# control-board.net
KiCad netlist of a schematic drawn in EAGLE
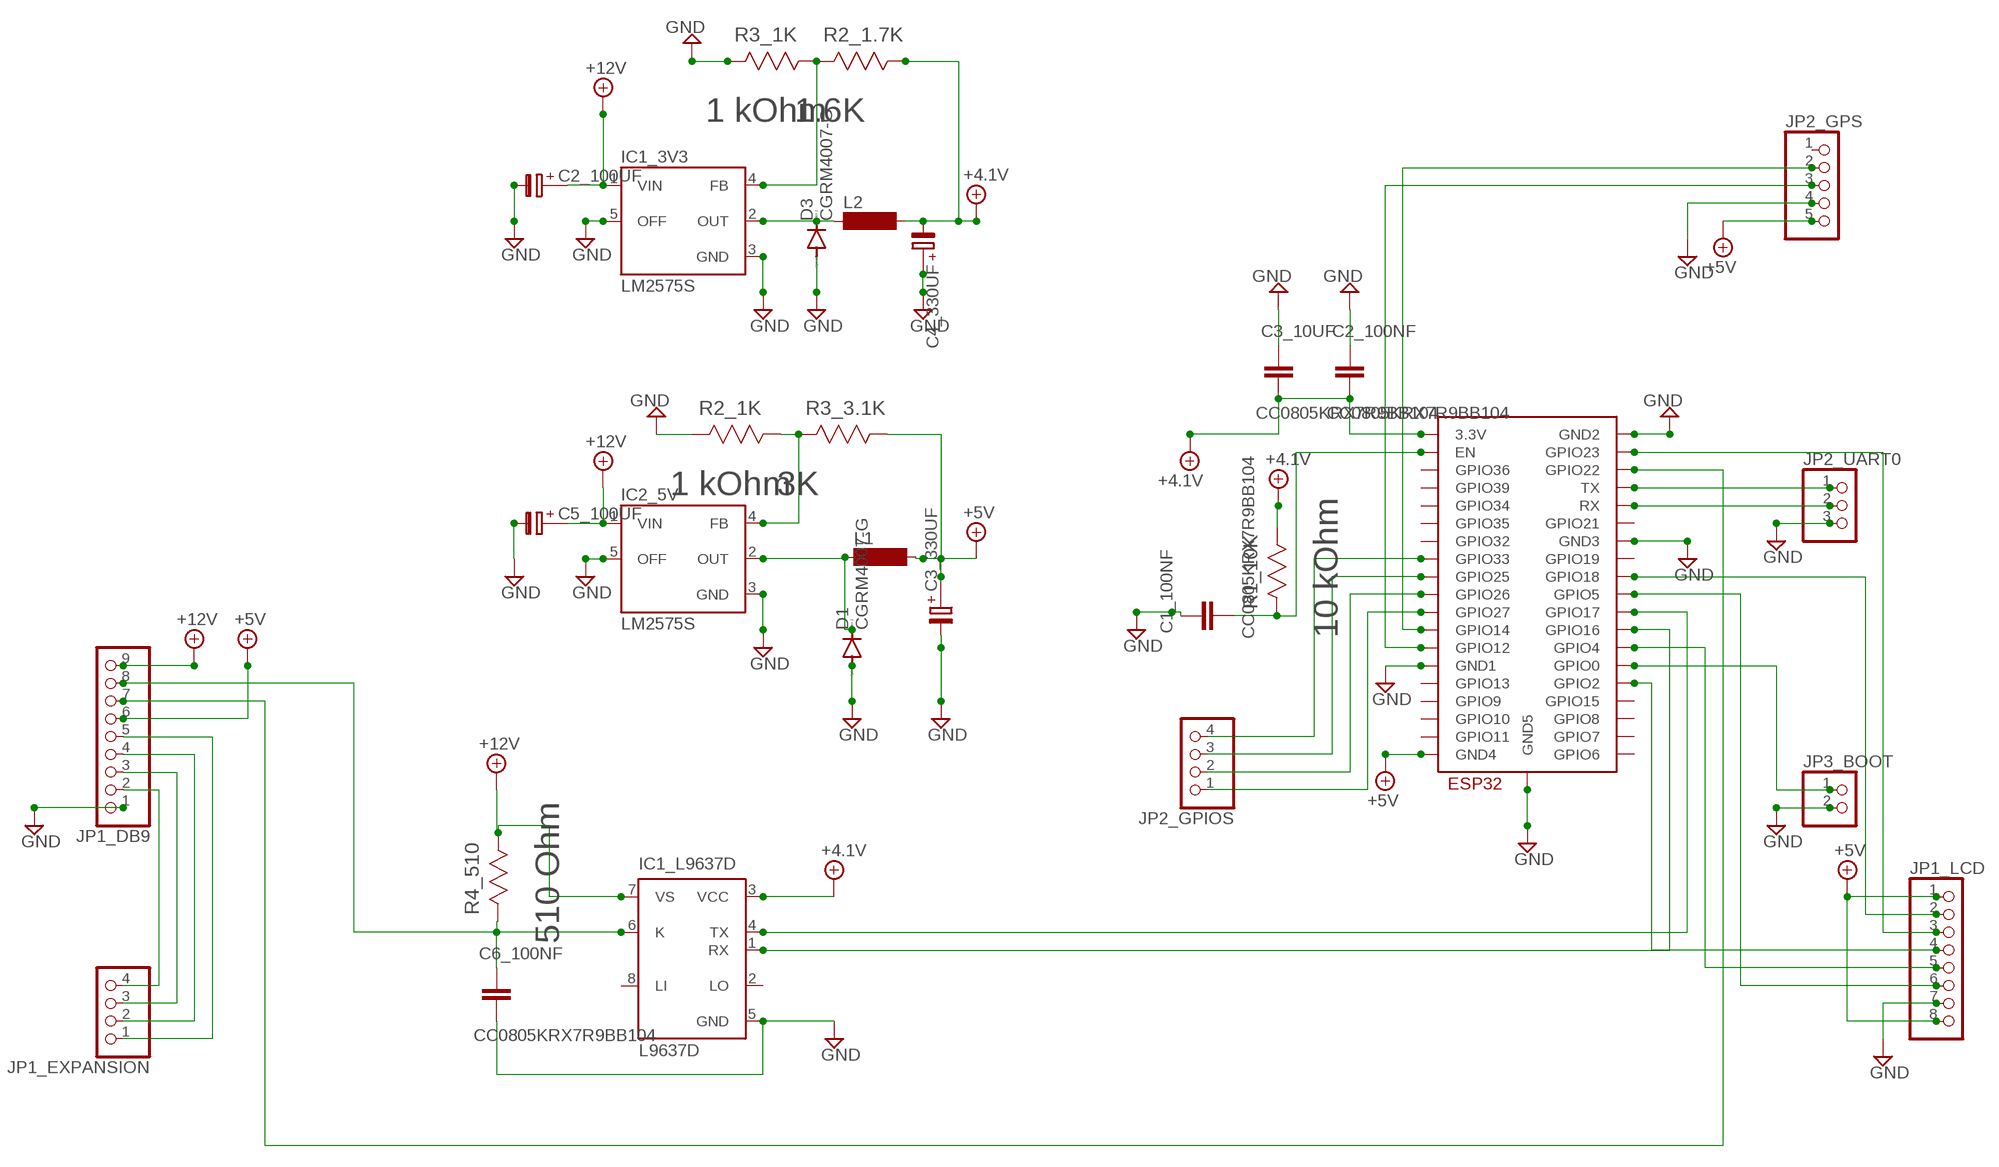
[diagram p0: schematic, sheet 1]

(export (version "E")
  (design (tool "Eeschema 10.0.6"))
  (components
    (comp (ref "C1_100NF")
      (value "CC0805KRX7R9BB104")
      (footprint "eagle-import:CAP_0805")
      (fields
        (field (name "DIGIKEY_PART_NUMBER") "311-1140-2-ND")
        (field (name "MANUFACTURER") "Yageo")
        (field (name "CREATED_BY") "PCBLayout.com")
      )
      (libsource (lib "eagle-import") (part "CC0805KRX7R9BB104"))
    )
    (comp (ref "C2_100NF")
      (value "CC0805KRX7R9BB104")
      (footprint "eagle-import:CAP_0805")
      (fields
        (field (name "DIGIKEY_PART_NUMBER") "311-1140-2-ND")
        (field (name "MANUFACTURER") "Yageo")
        (field (name "CREATED_BY") "PCBLayout.com")
      )
      (libsource (lib "eagle-import") (part "CC0805KRX7R9BB104"))
    )
    (comp (ref "C2_100UF")
      (value "C-PR-SMD-SV-E/F")
      (footprint "eagle-import:SV-E_F")
      (libsource (lib "eagle-import") (part "C-PR-SMD-SV-E/F"))
    )
    (comp (ref "C3_10UF")
      (value "CC0805KRX7R9BB104")
      (footprint "eagle-import:CAP_0805")
      (fields
        (field (name "DIGIKEY_PART_NUMBER") "311-1140-2-ND")
        (field (name "MANUFACTURER") "Yageo")
        (field (name "CREATED_BY") "PCBLayout.com")
      )
      (libsource (lib "eagle-import") (part "CC0805KRX7R9BB104"))
    )
    (comp (ref "C3_330UF")
      (value "C-PR-SMD-SV-D")
      (footprint "eagle-import:SV-D")
      (libsource (lib "eagle-import") (part "C-PR-SMD-SV-D"))
    )
    (comp (ref "C4_330UF")
      (value "C-PR-SMD-SV-D")
      (footprint "eagle-import:SV-D")
      (libsource (lib "eagle-import") (part "C-PR-SMD-SV-D"))
    )
    (comp (ref "C5_100UF")
      (value "C-PR-SMD-SV-E/F")
      (footprint "eagle-import:SV-E_F")
      (libsource (lib "eagle-import") (part "C-PR-SMD-SV-E/F"))
    )
    (comp (ref "C6_100NF")
      (value "CC0805KRX7R9BB104")
      (footprint "eagle-import:CAP_0805")
      (fields
        (field (name "DIGIKEY_PART_NUMBER") "311-1140-2-ND")
        (field (name "MANUFACTURER") "Yageo")
        (field (name "CREATED_BY") "PCBLayout.com")
      )
      (libsource (lib "eagle-import") (part "CC0805KRX7R9BB104"))
    )
    (comp (ref "D1")
      (value "CGRM4007-G")
      (footprint "eagle-import:SOD-123_MINI-SMA")
      (libsource (lib "eagle-import") (part "CGRM400-G7"))
    )
    (comp (ref "D3")
      (value "CGRM4007-G")
      (footprint "eagle-import:SOD-123_MINI-SMA")
      (libsource (lib "eagle-import") (part "CGRM400-G7"))
    )
    (comp (ref "ESP32")
      (value "ESP32-WROOM")
      (footprint "eagle-import:ESP32-WROOM")
      (libsource (lib "eagle-import") (part "ESP32-WROOM"))
    )
    (comp (ref "IC1_3V3")
      (value "LM2575S")
      (footprint "eagle-import:TO263-5")
      (libsource (lib "eagle-import") (part "LM2575S"))
    )
    (comp (ref "IC1_L9637D")
      (value "L9637D")
      (footprint "eagle-import:SO08")
      (libsource (lib "eagle-import") (part "L9637D"))
    )
    (comp (ref "IC2_5V")
      (value "LM2575S")
      (footprint "eagle-import:TO263-5")
      (libsource (lib "eagle-import") (part "LM2575S"))
    )
    (comp (ref "JP1_DB9")
      (value "PINHD-1X9/90")
      (footprint "eagle-import:1X09_90")
      (libsource (lib "eagle-import") (part "PINHD-1X9/90"))
    )
    (comp (ref "JP1_EXPANSION")
      (value "PINHD-1X4/90")
      (footprint "eagle-import:1X04_90")
      (libsource (lib "eagle-import") (part "PINHD-1X4/90"))
    )
    (comp (ref "JP1_LCD")
      (value "PINHD-1X8")
      (footprint "eagle-import:1X08")
      (libsource (lib "eagle-import") (part "PINHD-1X8"))
    )
    (comp (ref "JP2_GPIOS")
      (value "PINHD-1X4/90")
      (footprint "eagle-import:1X04_90")
      (libsource (lib "eagle-import") (part "PINHD-1X4/90"))
    )
    (comp (ref "JP2_GPS")
      (value "PINHD-1X5")
      (footprint "eagle-import:1X05")
      (libsource (lib "eagle-import") (part "PINHD-1X5"))
    )
    (comp (ref "JP2_UART0")
      (value "PINHD-1X3/90")
      (footprint "eagle-import:1X03_90")
      (libsource (lib "eagle-import") (part "PINHD-1X3/90"))
    )
    (comp (ref "JP3_BOOT")
      (value "PINHD-1X2/90")
      (footprint "eagle-import:1X02_90")
      (libsource (lib "eagle-import") (part "PINHD-1X2/90"))
    )
    (comp (ref "L1")
      (value "MS85")
      (footprint "eagle-import:MS85")
      (libsource (lib "eagle-import") (part "MS85"))
    )
    (comp (ref "L2")
      (value "MS85")
      (footprint "eagle-import:MS85")
      (libsource (lib "eagle-import") (part "MS85"))
    )
    (comp (ref "R1_10K")
      (value "10 kOhm")
      (footprint "eagle-import:RESC2013X65N")
      (fields (field (name "MPN") "ERA-6AEB103V") (field (name "TOLERANCE") "±0.1 %"))
      (libsource (lib "eagle-import") (part "ERA-6AEB103V"))
    )
    (comp (ref "R2_1.7K")
      (value "1.6K")
      (footprint "eagle-import:RESC2013X65N")
      (fields (field (name "MPN") "ERJP06F1601V") (field (name "TOLERANCE") "± 1%"))
      (libsource (lib "eagle-import") (part "ERJP06F1601V"))
    )
    (comp (ref "R2_1K")
      (value "1 kOhm")
      (footprint "eagle-import:RESC2013X65N")
      (fields (field (name "MPN") "ERA-6AEB102V") (field (name "TOLERANCE") "±0.1 %"))
      (libsource (lib "eagle-import") (part "ERA-6AEB102V"))
    )
    (comp (ref "R3_1K")
      (value "1 kOhm")
      (footprint "eagle-import:RESC2013X65N")
      (fields (field (name "MPN") "ERA-6AEB102V") (field (name "TOLERANCE") "±0.1 %"))
      (libsource (lib "eagle-import") (part "ERA-6AEB102V"))
    )
    (comp (ref "R3_3.1K")
      (value "3K")
      (footprint "eagle-import:RESC2013X65N")
      (fields (field (name "MPN") "ERJP06F3001V") (field (name "TOLERANCE") "± 1%"))
      (libsource (lib "eagle-import") (part "ERJP06F3001V"))
    )
    (comp (ref "R4_510")
      (value "510 Ohm")
      (footprint "eagle-import:RESC2013X65N")
      (fields (field (name "MPN") "ERA-6AEB511V") (field (name "TOLERANCE") "±0.1 %"))
      (libsource (lib "eagle-import") (part "ERA-6AEB511V"))
    )
  )
  (nets
    (net (code "1") (name "+4.1V") (class "Default")
      (node (ref "C2_100NF") (pin "2") (pinfunction "2_2") (pintype "passive"))
      (node (ref "C3_10UF") (pin "2") (pinfunction "2_2") (pintype "passive"))
      (node (ref "C4_330UF") (pin "-") (pinfunction "-_-") (pintype "passive"))
      (node (ref "ESP32") (pin "3V3") (pinfunction "3.3V_3V3") (pintype "bidirectional"))
      (node (ref "IC1_L9637D") (pin "3") (pinfunction "VCC_3") (pintype "power_in"))
      (node (ref "L2") (pin "2") (pinfunction "2_2") (pintype "passive"))
      (node (ref "R1_10K") (pin "1") (pinfunction "R1_1") (pintype "passive"))
      (node (ref "R2_1.7K") (pin "1") (pinfunction "R1_1") (pintype "passive"))
    )
    (net (code "2") (name "+5V") (class "Default")
      (node (ref "C3_330UF") (pin "+") (pinfunction "+_+") (pintype "passive"))
      (node (ref "ESP32") (pin "GND4") (pinfunction "GND4_GND4") (pintype "bidirectional"))
      (node (ref "JP1_DB9") (pin "6") (pinfunction "6_6") (pintype "passive"))
      (node (ref "JP1_LCD") (pin "1") (pinfunction "1_1") (pintype "passive"))
      (node (ref "JP1_LCD") (pin "8") (pinfunction "8_8") (pintype "passive"))
      (node (ref "JP2_GPS") (pin "5") (pinfunction "5_5") (pintype "passive"))
      (node (ref "L1") (pin "2") (pinfunction "2_2") (pintype "passive"))
      (node (ref "R3_3.1K") (pin "1") (pinfunction "R1_1") (pintype "passive"))
    )
    (net (code "3") (name "+12V") (class "Default")
      (node (ref "C2_100UF") (pin "+") (pinfunction "+_+") (pintype "passive"))
      (node (ref "C5_100UF") (pin "+") (pinfunction "+_+") (pintype "passive"))
      (node (ref "IC1_3V3") (pin "1") (pinfunction "VIN_1") (pintype "power_in"))
      (node (ref "IC1_L9637D") (pin "7") (pinfunction "VS_7") (pintype "power_in"))
      (node (ref "IC2_5V") (pin "1") (pinfunction "VIN_1") (pintype "power_in"))
      (node (ref "JP1_DB9") (pin "9") (pinfunction "9_9") (pintype "passive"))
      (node (ref "R4_510") (pin "1") (pinfunction "R1_1") (pintype "passive"))
    )
    (net (code "4") (name "GND") (class "Default")
      (node (ref "C1_100NF") (pin "1") (pinfunction "1_1") (pintype "passive"))
      (node (ref "C2_100NF") (pin "1") (pinfunction "1_1") (pintype "passive"))
      (node (ref "C2_100UF") (pin "-") (pinfunction "-_-") (pintype "passive"))
      (node (ref "C3_10UF") (pin "1") (pinfunction "1_1") (pintype "passive"))
      (node (ref "C3_330UF") (pin "-") (pinfunction "-_-") (pintype "passive"))
      (node (ref "C4_330UF") (pin "+") (pinfunction "+_+") (pintype "passive"))
      (node (ref "C5_100UF") (pin "-") (pinfunction "-_-") (pintype "passive"))
      (node (ref "C6_100NF") (pin "2") (pinfunction "2_2") (pintype "passive"))
      (node (ref "D1") (pin "A") (pinfunction "A_A") (pintype "passive"))
      (node (ref "D3") (pin "A") (pinfunction "A_A") (pintype "passive"))
      (node (ref "ESP32") (pin "GND1") (pinfunction "GND1_GND1") (pintype "bidirectional"))
      (node (ref "ESP32") (pin "GND2") (pinfunction "GND2_GND2") (pintype "bidirectional"))
      (node (ref "ESP32") (pin "GND3") (pinfunction "GND3_GND3") (pintype "bidirectional"))
      (node (ref "ESP32") (pin "GND5") (pinfunction "GND5_GND5") (pintype "bidirectional"))
      (node (ref "IC1_3V3") (pin "3") (pinfunction "GND_3") (pintype "power_in"))
      (node (ref "IC1_3V3") (pin "5") (pinfunction "OFF_5") (pintype "input"))
      (node (ref "IC1_L9637D") (pin "5") (pinfunction "GND_5") (pintype "power_in"))
      (node (ref "IC2_5V") (pin "3") (pinfunction "GND_3") (pintype "power_in"))
      (node (ref "IC2_5V") (pin "5") (pinfunction "OFF_5") (pintype "input"))
      (node (ref "JP1_DB9") (pin "1") (pinfunction "1_1") (pintype "passive"))
      (node (ref "JP1_LCD") (pin "7") (pinfunction "7_7") (pintype "passive"))
      (node (ref "JP2_GPS") (pin "4") (pinfunction "4_4") (pintype "passive"))
      (node (ref "JP2_UART0") (pin "3") (pinfunction "3_3") (pintype "passive"))
      (node (ref "JP3_BOOT") (pin "2") (pinfunction "2_2") (pintype "passive"))
      (node (ref "R2_1K") (pin "2") (pinfunction "R2_2") (pintype "passive"))
      (node (ref "R3_1K") (pin "2") (pinfunction "R2_2") (pintype "passive"))
    )
    (net (code "5") (name "Net-(ESP32-GPIO0)") (class "Default")
      (node (ref "ESP32") (pin "IO0") (pinfunction "GPIO0_IO0") (pintype "bidirectional"))
      (node (ref "JP3_BOOT") (pin "1") (pinfunction "1_1") (pintype "passive"))
    )
    (net (code "6") (name "Net-(ESP32-GPIO2)") (class "Default")
      (node (ref "ESP32") (pin "IO2") (pinfunction "GPIO2_IO2") (pintype "bidirectional"))
      (node (ref "JP1_LCD") (pin "4") (pinfunction "4_4") (pintype "passive"))
    )
    (net (code "7") (name "Net-(ESP32-GPIO4)") (class "Default")
      (node (ref "ESP32") (pin "IO4") (pinfunction "GPIO4_IO4") (pintype "bidirectional"))
      (node (ref "JP1_LCD") (pin "5") (pinfunction "5_5") (pintype "passive"))
    )
    (net (code "8") (name "Net-(ESP32-GPIO5)") (class "Default")
      (node (ref "ESP32") (pin "IO5") (pinfunction "GPIO5_IO5") (pintype "bidirectional"))
      (node (ref "JP1_LCD") (pin "6") (pinfunction "6_6") (pintype "passive"))
    )
    (net (code "9") (name "Net-(ESP32-GPIO12)") (class "Default")
      (node (ref "ESP32") (pin "IO12") (pinfunction "GPIO12_IO12") (pintype "bidirectional"))
      (node (ref "JP2_GPS") (pin "3") (pinfunction "3_3") (pintype "passive"))
    )
    (net (code "10") (name "Net-(ESP32-GPIO14)") (class "Default")
      (node (ref "ESP32") (pin "IO14") (pinfunction "GPIO14_IO14") (pintype "bidirectional"))
      (node (ref "JP2_GPS") (pin "2") (pinfunction "2_2") (pintype "passive"))
    )
    (net (code "11") (name "Net-(ESP32-GPIO16)") (class "Default")
      (node (ref "ESP32") (pin "IO16") (pinfunction "GPIO16_IO16") (pintype "bidirectional"))
      (node (ref "IC1_L9637D") (pin "1") (pinfunction "RX_1") (pintype "output"))
    )
    (net (code "12") (name "Net-(ESP32-GPIO17)") (class "Default")
      (node (ref "ESP32") (pin "IO17") (pinfunction "GPIO17_IO17") (pintype "bidirectional"))
      (node (ref "IC1_L9637D") (pin "4") (pinfunction "TX_4") (pintype "input"))
    )
    (net (code "13") (name "Net-(ESP32-GPIO18)") (class "Default")
      (node (ref "ESP32") (pin "IO18") (pinfunction "GPIO18_IO18") (pintype "bidirectional"))
      (node (ref "JP1_LCD") (pin "2") (pinfunction "2_2") (pintype "passive"))
    )
    (net (code "14") (name "Net-(ESP32-GPIO22)") (class "Default")
      (node (ref "ESP32") (pin "IO22") (pinfunction "GPIO22_IO22") (pintype "bidirectional"))
      (node (ref "JP1_DB9") (pin "7") (pinfunction "7_7") (pintype "passive"))
    )
    (net (code "15") (name "Net-(ESP32-GPIO23)") (class "Default")
      (node (ref "ESP32") (pin "IO23") (pinfunction "GPIO23_IO23") (pintype "bidirectional"))
      (node (ref "JP1_LCD") (pin "3") (pinfunction "3_3") (pintype "passive"))
    )
    (net (code "16") (name "Net-(ESP32-GPIO25)") (class "Default")
      (node (ref "ESP32") (pin "IO25") (pinfunction "GPIO25_IO25") (pintype "bidirectional"))
      (node (ref "JP2_GPIOS") (pin "3") (pinfunction "3_3") (pintype "passive"))
    )
    (net (code "17") (name "Net-(ESP32-GPIO26)") (class "Default")
      (node (ref "ESP32") (pin "IO26") (pinfunction "GPIO26_IO26") (pintype "bidirectional"))
      (node (ref "JP2_GPIOS") (pin "2") (pinfunction "2_2") (pintype "passive"))
    )
    (net (code "18") (name "Net-(ESP32-GPIO27)") (class "Default")
      (node (ref "ESP32") (pin "IO27") (pinfunction "GPIO27_IO27") (pintype "bidirectional"))
      (node (ref "JP2_GPIOS") (pin "1") (pinfunction "1_1") (pintype "passive"))
    )
    (net (code "19") (name "Net-(ESP32-GPIO33)") (class "Default")
      (node (ref "ESP32") (pin "IO33") (pinfunction "GPIO33_IO33") (pintype "bidirectional"))
      (node (ref "JP2_GPIOS") (pin "4") (pinfunction "4_4") (pintype "passive"))
    )
    (net (code "20") (name "Net-(ESP32-PadRX)") (class "Default")
      (node (ref "ESP32") (pin "RX") (pinfunction "RX_RX") (pintype "bidirectional"))
      (node (ref "JP2_UART0") (pin "2") (pinfunction "2_2") (pintype "passive"))
    )
    (net (code "21") (name "Net-(ESP32-PadTX)") (class "Default")
      (node (ref "ESP32") (pin "TX") (pinfunction "TX_TX") (pintype "bidirectional"))
      (node (ref "JP2_UART0") (pin "1") (pinfunction "1_1") (pintype "passive"))
    )
    (net (code "22") (name "Net-(IC1_3V3-FB)") (class "Default")
      (node (ref "IC1_3V3") (pin "4") (pinfunction "FB_4") (pintype "input"))
      (node (ref "R2_1.7K") (pin "2") (pinfunction "R2_2") (pintype "passive"))
      (node (ref "R3_1K") (pin "1") (pinfunction "R1_1") (pintype "passive"))
    )
    (net (code "23") (name "Net-(IC1_3V3-OUT)") (class "Default")
      (node (ref "D3") (pin "C") (pinfunction "C_C") (pintype "passive"))
      (node (ref "IC1_3V3") (pin "2") (pinfunction "OUT_2") (pintype "output"))
      (node (ref "L2") (pin "1") (pinfunction "1_1") (pintype "passive"))
    )
    (net (code "24") (name "Net-(IC1_L9637D-K)") (class "Default")
      (node (ref "C6_100NF") (pin "1") (pinfunction "1_1") (pintype "passive"))
      (node (ref "IC1_L9637D") (pin "6") (pinfunction "K_6") (pintype "input"))
      (node (ref "JP1_DB9") (pin "8") (pinfunction "8_8") (pintype "passive"))
      (node (ref "R4_510") (pin "2") (pinfunction "R2_2") (pintype "passive"))
    )
    (net (code "25") (name "Net-(IC2_5V-FB)") (class "Default")
      (node (ref "IC2_5V") (pin "4") (pinfunction "FB_4") (pintype "input"))
      (node (ref "R2_1K") (pin "1") (pinfunction "R1_1") (pintype "passive"))
      (node (ref "R3_3.1K") (pin "2") (pinfunction "R2_2") (pintype "passive"))
    )
    (net (code "26") (name "Net-(IC2_5V-OUT)") (class "Default")
      (node (ref "D1") (pin "C") (pinfunction "C_C") (pintype "passive"))
      (node (ref "IC2_5V") (pin "2") (pinfunction "OUT_2") (pintype "output"))
      (node (ref "L1") (pin "1") (pinfunction "1_1") (pintype "passive"))
    )
    (net (code "27") (name "Net-(JP1_DB9-Pad2)") (class "Default")
      (node (ref "JP1_DB9") (pin "2") (pinfunction "2_2") (pintype "passive"))
      (node (ref "JP1_EXPANSION") (pin "4") (pinfunction "4_4") (pintype "passive"))
    )
    (net (code "28") (name "Net-(JP1_DB9-Pad3)") (class "Default")
      (node (ref "JP1_DB9") (pin "3") (pinfunction "3_3") (pintype "passive"))
      (node (ref "JP1_EXPANSION") (pin "3") (pinfunction "3_3") (pintype "passive"))
    )
    (net (code "29") (name "Net-(JP1_DB9-Pad4)") (class "Default")
      (node (ref "JP1_DB9") (pin "4") (pinfunction "4_4") (pintype "passive"))
      (node (ref "JP1_EXPANSION") (pin "2") (pinfunction "2_2") (pintype "passive"))
    )
    (net (code "30") (name "Net-(JP1_DB9-Pad5)") (class "Default")
      (node (ref "JP1_DB9") (pin "5") (pinfunction "5_5") (pintype "passive"))
      (node (ref "JP1_EXPANSION") (pin "1") (pinfunction "1_1") (pintype "passive"))
    )
    (net (code "31") (name "Net-(R1_10K-R2)") (class "Default")
      (node (ref "C1_100NF") (pin "2") (pinfunction "2_2") (pintype "passive"))
      (node (ref "ESP32") (pin "EN") (pinfunction "EN_EN") (pintype "bidirectional"))
      (node (ref "R1_10K") (pin "2") (pinfunction "R2_2") (pintype "passive"))
    )
    (net (code "32") (name "unconnected-(ESP32-GPIO6-PadCLK)") (class "Default")
      (node (ref "ESP32") (pin "CLK") (pinfunction "GPIO6_CLK") (pintype "bidirectional"))
    )
    (net (code "33") (name "unconnected-(ESP32-GPIO7-PadSD0)") (class "Default")
      (node (ref "ESP32") (pin "SD0") (pinfunction "GPIO7_SD0") (pintype "bidirectional"))
    )
    (net (code "34") (name "unconnected-(ESP32-GPIO8-PadSD1)") (class "Default")
      (node (ref "ESP32") (pin "SD1") (pinfunction "GPIO8_SD1") (pintype "bidirectional"))
    )
    (net (code "35") (name "unconnected-(ESP32-GPIO9-PadSD2)") (class "Default")
      (node (ref "ESP32") (pin "SD2") (pinfunction "GPIO9_SD2") (pintype "bidirectional"))
    )
    (net (code "36") (name "unconnected-(ESP32-GPIO10-PadSD3)") (class "Default")
      (node (ref "ESP32") (pin "SD3") (pinfunction "GPIO10_SD3") (pintype "bidirectional"))
    )
    (net (code "37") (name "unconnected-(ESP32-GPIO11-PadCMD)") (class "Default")
      (node (ref "ESP32") (pin "CMD") (pinfunction "GPIO11_CMD") (pintype "bidirectional"))
    )
    (net (code "38") (name "unconnected-(ESP32-GPIO13-PadIO13)") (class "Default")
      (node (ref "ESP32") (pin "IO13") (pinfunction "GPIO13_IO13") (pintype "bidirectional"))
    )
    (net (code "39") (name "unconnected-(ESP32-GPIO15-PadIO15)") (class "Default")
      (node (ref "ESP32") (pin "IO15") (pinfunction "GPIO15_IO15") (pintype "bidirectional"))
    )
    (net (code "40") (name "unconnected-(ESP32-GPIO19-PadIO19)") (class "Default")
      (node (ref "ESP32") (pin "IO19") (pinfunction "GPIO19_IO19") (pintype "bidirectional"))
    )
    (net (code "41") (name "unconnected-(ESP32-GPIO21-PadIO21)") (class "Default")
      (node (ref "ESP32") (pin "IO21") (pinfunction "GPIO21_IO21") (pintype "bidirectional"))
    )
    (net (code "42") (name "unconnected-(ESP32-GPIO32-PadIO32)") (class "Default")
      (node (ref "ESP32") (pin "IO32") (pinfunction "GPIO32_IO32") (pintype "bidirectional"))
    )
    (net (code "43") (name "unconnected-(ESP32-GPIO34-PadIO34)") (class "Default")
      (node (ref "ESP32") (pin "IO34") (pinfunction "GPIO34_IO34") (pintype "bidirectional"))
    )
    (net (code "44") (name "unconnected-(ESP32-GPIO35-PadIO35)") (class "Default")
      (node (ref "ESP32") (pin "IO35") (pinfunction "GPIO35_IO35") (pintype "bidirectional"))
    )
    (net (code "45") (name "unconnected-(ESP32-GPIO36-PadSENSOR_VP)") (class "Default")
      (node (ref "ESP32") (pin "SENSOR_VP") (pinfunction "GPIO36_SENSOR_VP") (pintype "bidirectional"))
    )
    (net (code "46") (name "unconnected-(ESP32-GPIO39-PadSENSOR_VN)") (class "Default")
      (node (ref "ESP32") (pin "SENSOR_VN") (pinfunction "GPIO39_SENSOR_VN") (pintype "bidirectional"))
    )
    (net (code "47") (name "unconnected-(IC1_L9637D-LI-Pad8)") (class "Default")
      (node (ref "IC1_L9637D") (pin "8") (pinfunction "LI_8") (pintype "input"))
    )
    (net (code "48") (name "unconnected-(IC1_L9637D-LO-Pad2)") (class "Default")
      (node (ref "IC1_L9637D") (pin "2") (pinfunction "LO_2") (pintype "output"))
    )
    (net (code "49") (name "unconnected-(JP2_GPS-Pad1)") (class "Default")
      (node (ref "JP2_GPS") (pin "1") (pinfunction "1_1") (pintype "passive"))
    )
  )
)
